# 16052.net
KiCad netlist of a schematic drawn in EAGLE
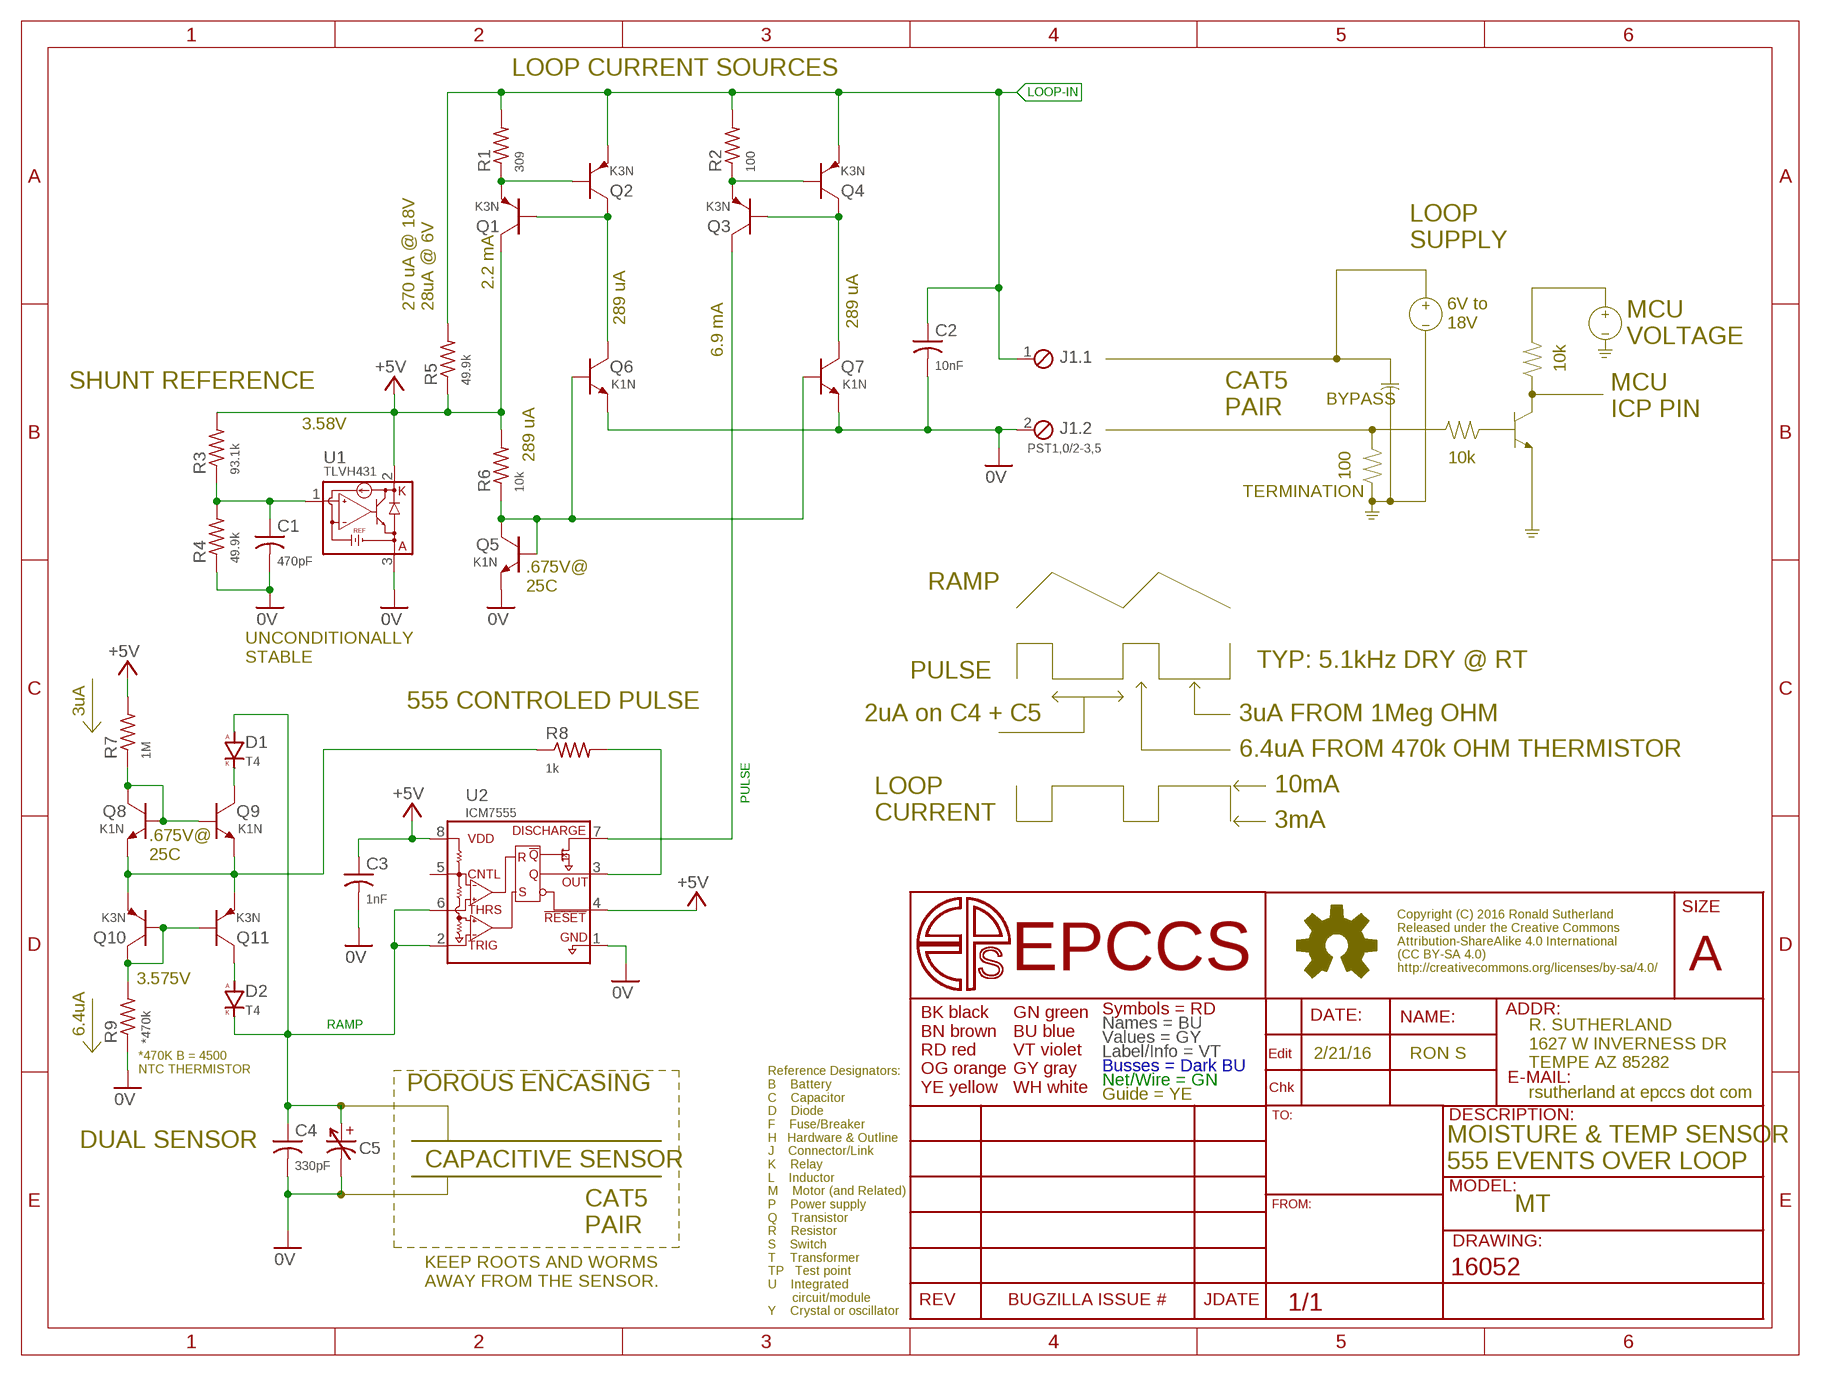
[diagram p0: schematic, sheet 1]

(export (version "E")
  (design (tool "Eeschema 10.0.6"))
  (components
    (comp (ref "C1")
      (value "470pF")
      (footprint "eagle-import:C0603(1608)")
      (libsource (lib "eagle-import") (part "CC0603A"))
    )
    (comp (ref "C2")
      (value "10nF")
      (footprint "eagle-import:C0603(1608)")
      (libsource (lib "eagle-import") (part "CC0603A"))
    )
    (comp (ref "C3")
      (value "1nF")
      (footprint "eagle-import:C0603(1608)")
      (libsource (lib "eagle-import") (part "CC0603A"))
    )
    (comp (ref "C4")
      (value "330pF")
      (footprint "eagle-import:C0603(1608)")
      (libsource (lib "eagle-import") (part "CC0603A"))
    )
    (comp (ref "C5")
      (value "HS1101")
      (footprint "eagle-import:HS1101")
      (libsource (lib "eagle-import") (part "HS1101"))
    )
    (comp (ref "D1")
      (value "T4")
      (footprint "eagle-import:SOD123")
      (libsource (lib "eagle-import") (part "DSOD123"))
    )
    (comp (ref "D2")
      (value "T4")
      (footprint "eagle-import:SOD123")
      (libsource (lib "eagle-import") (part "DSOD123"))
    )
    (comp (ref "J1")
      (value "PST1,0/2-3,5")
      (footprint "eagle-import:MCV2")
      (libsource (lib "eagle-import") (part "MCV2"))
    )
    (comp (ref "Q1")
      (value "K3N")
      (footprint "eagle-import:SOT23")
      (libsource (lib "eagle-import") (part "PNPSOT23"))
    )
    (comp (ref "Q2")
      (value "K3N")
      (footprint "eagle-import:SOT23")
      (libsource (lib "eagle-import") (part "PNPSOT23"))
    )
    (comp (ref "Q3")
      (value "K3N")
      (footprint "eagle-import:SOT23")
      (libsource (lib "eagle-import") (part "PNPSOT23"))
    )
    (comp (ref "Q4")
      (value "K3N")
      (footprint "eagle-import:SOT23")
      (libsource (lib "eagle-import") (part "PNPSOT23"))
    )
    (comp (ref "Q5")
      (value "K1N")
      (footprint "eagle-import:SOT23")
      (libsource (lib "eagle-import") (part "NPNSOT23"))
    )
    (comp (ref "Q6")
      (value "K1N")
      (footprint "eagle-import:SOT23")
      (libsource (lib "eagle-import") (part "NPNSOT23"))
    )
    (comp (ref "Q7")
      (value "K1N")
      (footprint "eagle-import:SOT23")
      (libsource (lib "eagle-import") (part "NPNSOT23"))
    )
    (comp (ref "Q8")
      (value "K1N")
      (footprint "eagle-import:SOT23")
      (libsource (lib "eagle-import") (part "NPNSOT23"))
    )
    (comp (ref "Q9")
      (value "K1N")
      (footprint "eagle-import:SOT23")
      (libsource (lib "eagle-import") (part "NPNSOT23"))
    )
    (comp (ref "Q10")
      (value "K3N")
      (footprint "eagle-import:SOT23")
      (libsource (lib "eagle-import") (part "PNPSOT23"))
    )
    (comp (ref "Q11")
      (value "K3N")
      (footprint "eagle-import:SOT23")
      (libsource (lib "eagle-import") (part "PNPSOT23"))
    )
    (comp (ref "R1")
      (value "309")
      (footprint "eagle-import:C0805(2012)")
      (libsource (lib "eagle-import") (part "R0805"))
    )
    (comp (ref "R2")
      (value "100")
      (footprint "eagle-import:C0805(2012)")
      (libsource (lib "eagle-import") (part "R0805"))
    )
    (comp (ref "R3")
      (value "93.1k")
      (footprint "eagle-import:C0805(2012)")
      (libsource (lib "eagle-import") (part "R0805"))
    )
    (comp (ref "R4")
      (value "49.9k")
      (footprint "eagle-import:C0805(2012)")
      (libsource (lib "eagle-import") (part "R0805"))
    )
    (comp (ref "R5")
      (value "49.9k")
      (footprint "eagle-import:C0805(2012)")
      (libsource (lib "eagle-import") (part "R0805"))
    )
    (comp (ref "R6")
      (value "10k")
      (footprint "eagle-import:C0805(2012)")
      (libsource (lib "eagle-import") (part "R0805"))
    )
    (comp (ref "R7")
      (value "1M")
      (footprint "eagle-import:C0805(2012)")
      (libsource (lib "eagle-import") (part "R0805"))
    )
    (comp (ref "R8")
      (value "1k")
      (footprint "eagle-import:C0805(2012)")
      (libsource (lib "eagle-import") (part "R0805"))
    )
    (comp (ref "R9")
      (value "*470k")
      (footprint "eagle-import:C0805(2012)")
      (libsource (lib "eagle-import") (part "R0805"))
    )
    (comp (ref "U1")
      (value "TLVH431")
      (footprint "eagle-import:SOT23")
      (libsource (lib "eagle-import") (part "TL432SOT23"))
    )
    (comp (ref "U2")
      (value "ICM7555")
      (footprint "eagle-import:SOIC8")
      (libsource (lib "eagle-import") (part "ICM7555"))
    )
  )
  (nets
    (net (code "1") (name "+5V") (class "Default")
      (node (ref "C3") (pin "1") (pinfunction "1_1") (pintype "passive"))
      (node (ref "Q1") (pin "C") (pinfunction "C_C") (pintype "passive"))
      (node (ref "R3") (pin "2") (pinfunction "2_2") (pintype "passive"))
      (node (ref "R5") (pin "1") (pinfunction "1_1") (pintype "passive"))
      (node (ref "R6") (pin "2") (pinfunction "2_2") (pintype "passive"))
      (node (ref "R7") (pin "2") (pinfunction "2_2") (pintype "passive"))
      (node (ref "U1") (pin "2") (pinfunction "K_2") (pintype "bidirectional"))
      (node (ref "U2") (pin "4") (pinfunction "~{RESET}_4") (pintype "input"))
      (node (ref "U2") (pin "8") (pinfunction "VDD_8") (pintype "power_in"))
    )
    (net (code "2") (name "/PULSE") (class "Default")
      (node (ref "Q3") (pin "C") (pinfunction "C_C") (pintype "passive"))
      (node (ref "U2") (pin "7") (pinfunction "DISCHARGE_7") (pintype "output"))
    )
    (net (code "3") (name "/RAMP") (class "Default")
      (node (ref "C4") (pin "1") (pinfunction "1_1") (pintype "passive"))
      (node (ref "C5") (pin "1") (pinfunction "1_1") (pintype "passive"))
      (node (ref "D1") (pin "A") (pinfunction "A_A") (pintype "passive"))
      (node (ref "D2") (pin "C") (pinfunction "K_C") (pintype "passive"))
      (node (ref "U2") (pin "2") (pinfunction "TRIG_2") (pintype "input"))
      (node (ref "U2") (pin "6") (pinfunction "THRS_6") (pintype "input"))
    )
    (net (code "4") (name "0V") (class "Default")
      (node (ref "C1") (pin "2") (pinfunction "2_2") (pintype "passive"))
      (node (ref "C2") (pin "2") (pinfunction "2_2") (pintype "passive"))
      (node (ref "C3") (pin "2") (pinfunction "2_2") (pintype "passive"))
      (node (ref "C4") (pin "2") (pinfunction "2_2") (pintype "passive"))
      (node (ref "C5") (pin "2") (pinfunction "2_2") (pintype "passive"))
      (node (ref "J1") (pin "2") (pinfunction "1_2") (pintype "passive"))
      (node (ref "Q5") (pin "E") (pinfunction "E_E") (pintype "passive"))
      (node (ref "Q6") (pin "E") (pinfunction "E_E") (pintype "passive"))
      (node (ref "Q7") (pin "E") (pinfunction "E_E") (pintype "passive"))
      (node (ref "R4") (pin "1") (pinfunction "1_1") (pintype "passive"))
      (node (ref "R9") (pin "1") (pinfunction "1_1") (pintype "passive"))
      (node (ref "U1") (pin "3") (pinfunction "A_3") (pintype "bidirectional"))
      (node (ref "U2") (pin "1") (pinfunction "GND_1") (pintype "power_in"))
    )
    (net (code "5") (name "LOOP-IN") (class "Default")
      (node (ref "C2") (pin "1") (pinfunction "1_1") (pintype "passive"))
      (node (ref "J1") (pin "1") (pinfunction "1_1") (pintype "passive"))
      (node (ref "Q2") (pin "E") (pinfunction "E_E") (pintype "passive"))
      (node (ref "Q4") (pin "E") (pinfunction "E_E") (pintype "passive"))
      (node (ref "R1") (pin "2") (pinfunction "2_2") (pintype "passive"))
      (node (ref "R2") (pin "2") (pinfunction "2_2") (pintype "passive"))
      (node (ref "R5") (pin "2") (pinfunction "2_2") (pintype "passive"))
    )
    (net (code "6") (name "Net-(D1-K)") (class "Default")
      (node (ref "D1") (pin "C") (pinfunction "K_C") (pintype "passive"))
      (node (ref "Q9") (pin "C") (pinfunction "C_C") (pintype "passive"))
    )
    (net (code "7") (name "Net-(D2-PadA)") (class "Default")
      (node (ref "D2") (pin "A") (pinfunction "A_A") (pintype "passive"))
      (node (ref "Q11") (pin "C") (pinfunction "C_C") (pintype "passive"))
    )
    (net (code "8") (name "Net-(Q1-PadB)") (class "Default")
      (node (ref "Q1") (pin "B") (pinfunction "B_B") (pintype "passive"))
      (node (ref "Q2") (pin "C") (pinfunction "C_C") (pintype "passive"))
      (node (ref "Q6") (pin "C") (pinfunction "C_C") (pintype "passive"))
    )
    (net (code "9") (name "Net-(Q1-PadE)") (class "Default")
      (node (ref "Q1") (pin "E") (pinfunction "E_E") (pintype "passive"))
      (node (ref "Q2") (pin "B") (pinfunction "B_B") (pintype "passive"))
      (node (ref "R1") (pin "1") (pinfunction "1_1") (pintype "passive"))
    )
    (net (code "10") (name "Net-(Q3-PadB)") (class "Default")
      (node (ref "Q3") (pin "B") (pinfunction "B_B") (pintype "passive"))
      (node (ref "Q4") (pin "C") (pinfunction "C_C") (pintype "passive"))
      (node (ref "Q7") (pin "C") (pinfunction "C_C") (pintype "passive"))
    )
    (net (code "11") (name "Net-(Q3-PadE)") (class "Default")
      (node (ref "Q3") (pin "E") (pinfunction "E_E") (pintype "passive"))
      (node (ref "Q4") (pin "B") (pinfunction "B_B") (pintype "passive"))
      (node (ref "R2") (pin "1") (pinfunction "1_1") (pintype "passive"))
    )
    (net (code "12") (name "Net-(Q5-PadB)") (class "Default")
      (node (ref "Q5") (pin "B") (pinfunction "B_B") (pintype "passive"))
      (node (ref "Q5") (pin "C") (pinfunction "C_C") (pintype "passive"))
      (node (ref "Q6") (pin "B") (pinfunction "B_B") (pintype "passive"))
      (node (ref "Q7") (pin "B") (pinfunction "B_B") (pintype "passive"))
      (node (ref "R6") (pin "1") (pinfunction "1_1") (pintype "passive"))
    )
    (net (code "13") (name "Net-(Q8-PadB)") (class "Default")
      (node (ref "Q8") (pin "B") (pinfunction "B_B") (pintype "passive"))
      (node (ref "Q8") (pin "C") (pinfunction "C_C") (pintype "passive"))
      (node (ref "Q9") (pin "B") (pinfunction "B_B") (pintype "passive"))
      (node (ref "R7") (pin "1") (pinfunction "1_1") (pintype "passive"))
    )
    (net (code "14") (name "Net-(Q10-PadB)") (class "Default")
      (node (ref "Q10") (pin "B") (pinfunction "B_B") (pintype "passive"))
      (node (ref "Q10") (pin "C") (pinfunction "C_C") (pintype "passive"))
      (node (ref "Q11") (pin "B") (pinfunction "B_B") (pintype "passive"))
      (node (ref "R9") (pin "2") (pinfunction "2_2") (pintype "passive"))
    )
    (net (code "15") (name "Net-(Q10-PadE)") (class "Default")
      (node (ref "Q10") (pin "E") (pinfunction "E_E") (pintype "passive"))
      (node (ref "Q11") (pin "E") (pinfunction "E_E") (pintype "passive"))
      (node (ref "Q8") (pin "E") (pinfunction "E_E") (pintype "passive"))
      (node (ref "Q9") (pin "E") (pinfunction "E_E") (pintype "passive"))
      (node (ref "R8") (pin "1") (pinfunction "1_1") (pintype "passive"))
    )
    (net (code "16") (name "Net-(U1-REF)") (class "Default")
      (node (ref "C1") (pin "1") (pinfunction "1_1") (pintype "passive"))
      (node (ref "R3") (pin "1") (pinfunction "1_1") (pintype "passive"))
      (node (ref "R4") (pin "2") (pinfunction "2_2") (pintype "passive"))
      (node (ref "U1") (pin "1") (pinfunction "REF_1") (pintype "bidirectional"))
    )
    (net (code "17") (name "Net-(U2-OUT)") (class "Default")
      (node (ref "R8") (pin "2") (pinfunction "2_2") (pintype "passive"))
      (node (ref "U2") (pin "3") (pinfunction "OUT_3") (pintype "output"))
    )
    (net (code "18") (name "unconnected-(U2-CNTL-Pad5)") (class "Default")
      (node (ref "U2") (pin "5") (pinfunction "CNTL_5") (pintype "bidirectional"))
    )
  )
)
